# eth_conn.net
KiCad netlist of a schematic drawn in Altium Designer
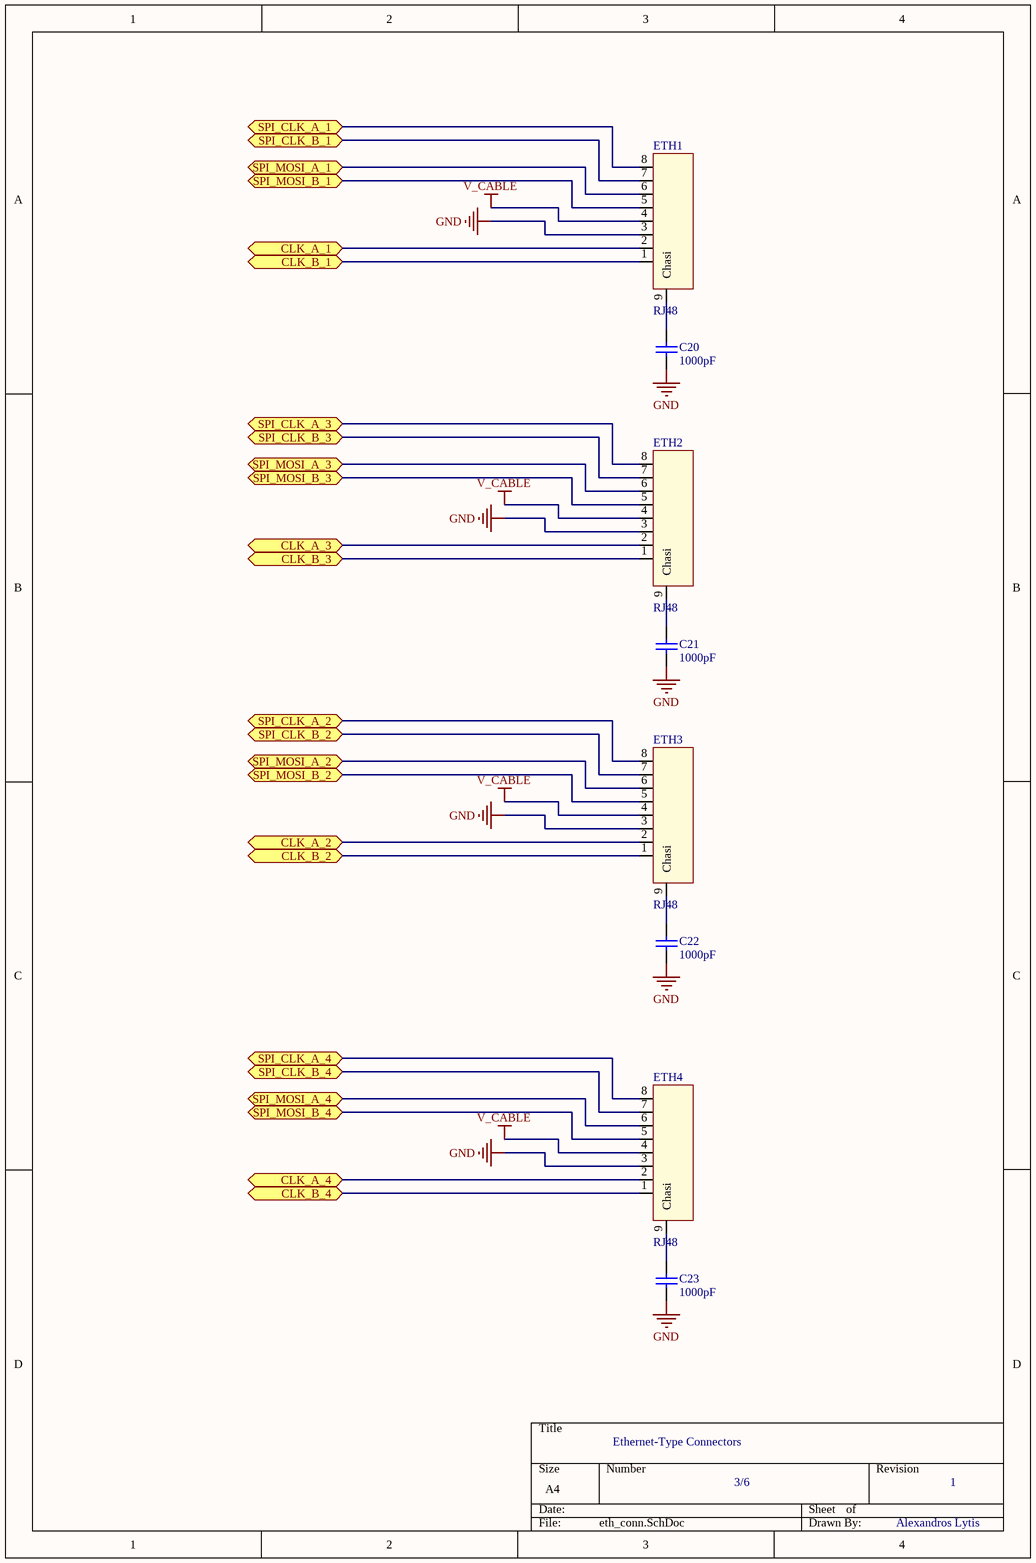
[diagram p0: eth_conn.SchDoc]

(export (version "E")
  (design (tool "Eeschema 10.0.6"))
  (components
    (comp (ref "C20")
      (value "1000pF")
      (footprint "CAP0603")
      (description "Capacitor (Semiconductor SIM Model)")
      (fields (field (name "Comment") "Cap Semi") (field (name "PUBLISHER") "Altium Limited"))
      (libsource (lib "Miscellaneous Devices") (part "Cap Semi"))
    )
    (comp (ref "C21")
      (value "1000pF")
      (footprint "CAP0603")
      (description "Capacitor (Semiconductor SIM Model)")
      (fields (field (name "Comment") "Cap Semi") (field (name "PUBLISHER") "Altium Limited"))
      (libsource (lib "Miscellaneous Devices") (part "Cap Semi"))
    )
    (comp (ref "C22")
      (value "1000pF")
      (footprint "CAP0603")
      (description "Capacitor (Semiconductor SIM Model)")
      (fields (field (name "Comment") "Cap Semi") (field (name "PUBLISHER") "Altium Limited"))
      (libsource (lib "Miscellaneous Devices") (part "Cap Semi"))
    )
    (comp (ref "C23")
      (value "1000pF")
      (footprint "CAP0603")
      (description "Capacitor (Semiconductor SIM Model)")
      (fields (field (name "Comment") "Cap Semi") (field (name "PUBLISHER") "Altium Limited"))
      (libsource (lib "Miscellaneous Devices") (part "Cap Semi"))
    )
    (comp (ref "ETH1")
      (value "RJ48")
      (footprint "TE modular Jack RJ45")
      (libsource (lib "Custom_Libraries") (part "Ethernet Jack"))
    )
    (comp (ref "ETH2")
      (value "RJ48")
      (footprint "TE modular Jack RJ45")
      (libsource (lib "Custom_Libraries") (part "Ethernet Jack"))
    )
    (comp (ref "ETH3")
      (value "RJ48")
      (footprint "TE modular Jack RJ45")
      (libsource (lib "Custom_Libraries") (part "Ethernet Jack"))
    )
    (comp (ref "ETH4")
      (value "RJ48")
      (footprint "TE modular Jack RJ45")
      (libsource (lib "Custom_Libraries") (part "Ethernet Jack"))
    )
  )
  (nets
    (net (code "1") (name "/CLK_A_1") (class "Default") (node (ref "ETH1") (pin "2") (pintype "passive")))
    (net (code "2") (name "/CLK_A_2") (class "Default") (node (ref "ETH3") (pin "2") (pintype "passive")))
    (net (code "3") (name "/CLK_A_3") (class "Default") (node (ref "ETH2") (pin "2") (pintype "passive")))
    (net (code "4") (name "/CLK_A_4") (class "Default") (node (ref "ETH4") (pin "2") (pintype "passive")))
    (net (code "5") (name "/CLK_B_1") (class "Default") (node (ref "ETH1") (pin "1") (pintype "passive")))
    (net (code "6") (name "/CLK_B_2") (class "Default") (node (ref "ETH3") (pin "1") (pintype "passive")))
    (net (code "7") (name "/CLK_B_3") (class "Default") (node (ref "ETH2") (pin "1") (pintype "passive")))
    (net (code "8") (name "/CLK_B_4") (class "Default") (node (ref "ETH4") (pin "1") (pintype "passive")))
    (net (code "9") (name "/SPI_CLK_A_1") (class "Default") (node (ref "ETH1") (pin "8") (pintype "passive")))
    (net (code "10") (name "/SPI_CLK_A_2") (class "Default")
      (node (ref "ETH3") (pin "8") (pintype "passive"))
    )
    (net (code "11") (name "/SPI_CLK_A_3") (class "Default")
      (node (ref "ETH2") (pin "8") (pintype "passive"))
    )
    (net (code "12") (name "/SPI_CLK_A_4") (class "Default")
      (node (ref "ETH4") (pin "8") (pintype "passive"))
    )
    (net (code "13") (name "/SPI_CLK_B_1") (class "Default")
      (node (ref "ETH1") (pin "7") (pintype "passive"))
    )
    (net (code "14") (name "/SPI_CLK_B_2") (class "Default")
      (node (ref "ETH3") (pin "7") (pintype "passive"))
    )
    (net (code "15") (name "/SPI_CLK_B_3") (class "Default")
      (node (ref "ETH2") (pin "7") (pintype "passive"))
    )
    (net (code "16") (name "/SPI_CLK_B_4") (class "Default")
      (node (ref "ETH4") (pin "7") (pintype "passive"))
    )
    (net (code "17") (name "/SPI_MOSI_A_1") (class "Default")
      (node (ref "ETH1") (pin "6") (pintype "passive"))
    )
    (net (code "18") (name "/SPI_MOSI_A_2") (class "Default")
      (node (ref "ETH3") (pin "6") (pintype "passive"))
    )
    (net (code "19") (name "/SPI_MOSI_A_3") (class "Default")
      (node (ref "ETH2") (pin "6") (pintype "passive"))
    )
    (net (code "20") (name "/SPI_MOSI_A_4") (class "Default")
      (node (ref "ETH4") (pin "6") (pintype "passive"))
    )
    (net (code "21") (name "/SPI_MOSI_B_1") (class "Default")
      (node (ref "ETH1") (pin "5") (pintype "passive"))
    )
    (net (code "22") (name "/SPI_MOSI_B_2") (class "Default")
      (node (ref "ETH3") (pin "5") (pintype "passive"))
    )
    (net (code "23") (name "/SPI_MOSI_B_3") (class "Default")
      (node (ref "ETH2") (pin "5") (pintype "passive"))
    )
    (net (code "24") (name "/SPI_MOSI_B_4") (class "Default")
      (node (ref "ETH4") (pin "5") (pintype "passive"))
    )
    (net (code "25") (name "GND") (class "Default")
      (node (ref "C20") (pin "1") (pinfunction "1_1") (pintype "passive"))
      (node (ref "C21") (pin "1") (pinfunction "1_1") (pintype "passive"))
      (node (ref "C22") (pin "1") (pinfunction "1_1") (pintype "passive"))
      (node (ref "C23") (pin "1") (pinfunction "1_1") (pintype "passive"))
      (node (ref "ETH1") (pin "3") (pintype "passive"))
      (node (ref "ETH2") (pin "3") (pintype "passive"))
      (node (ref "ETH3") (pin "3") (pintype "passive"))
      (node (ref "ETH4") (pin "3") (pintype "passive"))
    )
    (net (code "26") (name "Net-(ETH1-Chasi)") (class "Default")
      (node (ref "C20") (pin "2") (pinfunction "2_2") (pintype "passive"))
      (node (ref "ETH1") (pin "9") (pinfunction "Chasi_9") (pintype "passive"))
    )
    (net (code "27") (name "Net-(ETH2-Chasi)") (class "Default")
      (node (ref "C21") (pin "2") (pinfunction "2_2") (pintype "passive"))
      (node (ref "ETH2") (pin "9") (pinfunction "Chasi_9") (pintype "passive"))
    )
    (net (code "28") (name "Net-(ETH3-Chasi)") (class "Default")
      (node (ref "C22") (pin "2") (pinfunction "2_2") (pintype "passive"))
      (node (ref "ETH3") (pin "9") (pinfunction "Chasi_9") (pintype "passive"))
    )
    (net (code "29") (name "Net-(ETH4-Chasi)") (class "Default")
      (node (ref "C23") (pin "2") (pinfunction "2_2") (pintype "passive"))
      (node (ref "ETH4") (pin "9") (pinfunction "Chasi_9") (pintype "passive"))
    )
    (net (code "30") (name "V_CABLE") (class "Default")
      (node (ref "ETH1") (pin "4") (pintype "passive"))
      (node (ref "ETH2") (pin "4") (pintype "passive"))
      (node (ref "ETH3") (pin "4") (pintype "passive"))
      (node (ref "ETH4") (pin "4") (pintype "passive"))
    )
  )
)
